# ArduinoSchematic.net
KiCad netlist of a schematic drawn in Altium Designer
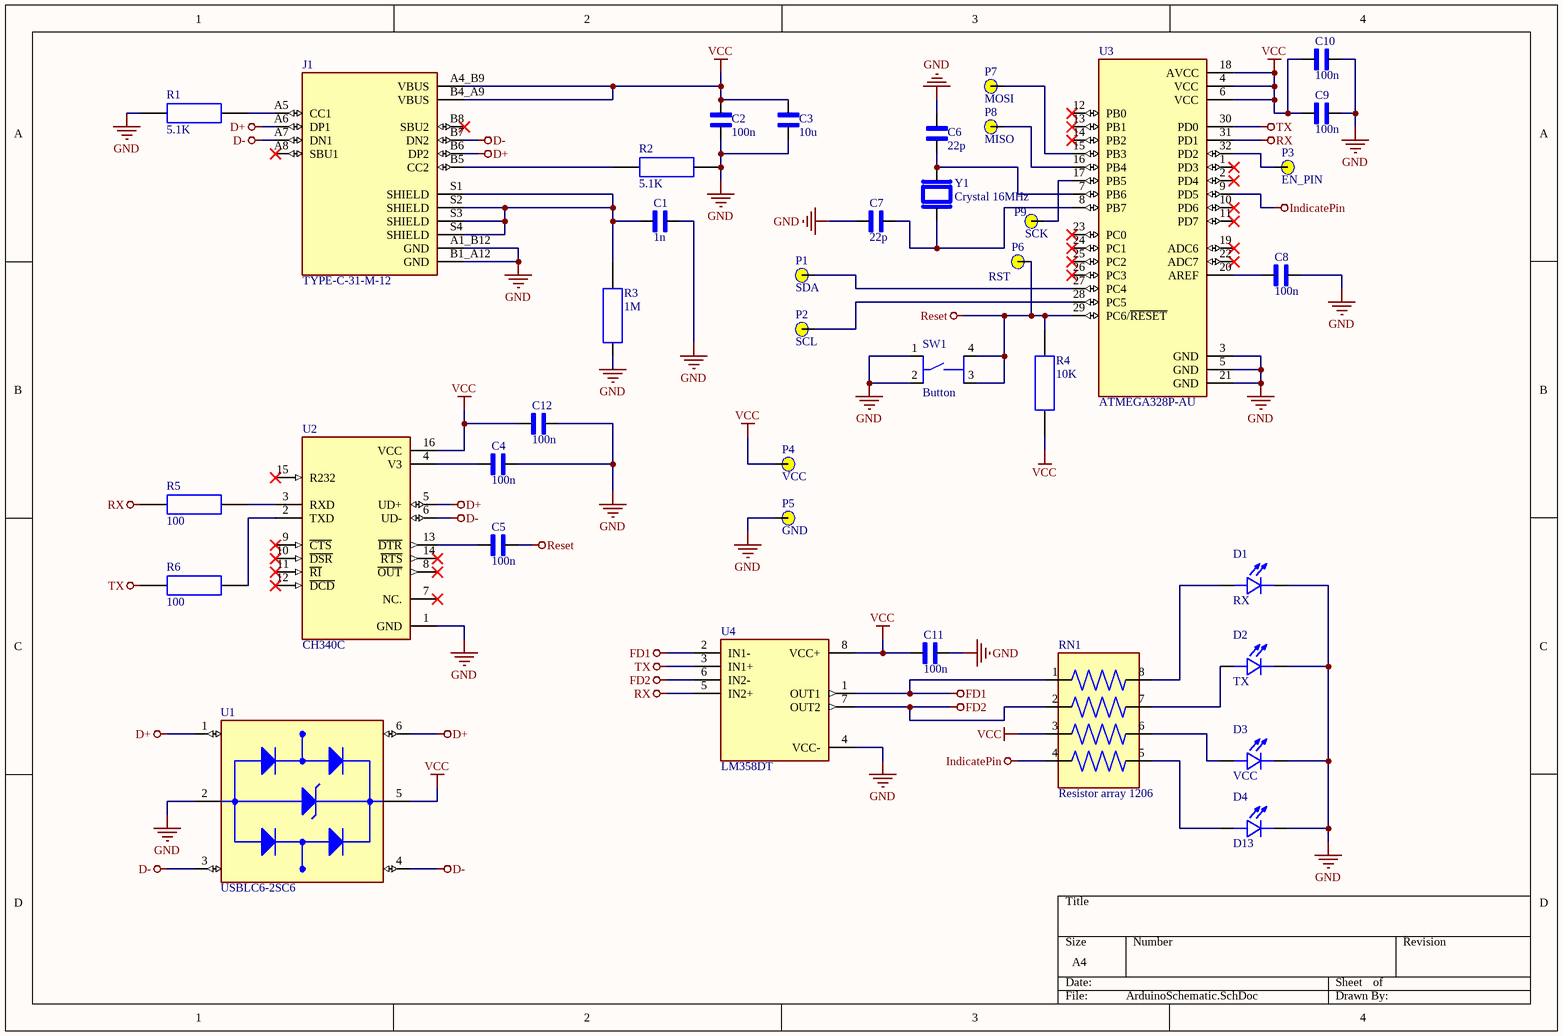
[diagram p0: ArduinoSchematic.SchDoc]

(export (version "E")
  (design (tool "Eeschema 10.0.6"))
  (components
    (comp (ref "C1")
      (value "1n")
      (footprint "Capacitor 1206")
      (fields (field (name "MF") "AVX") (field (name "MP") "12061C225K4T2A"))
      (libsource (lib "") (part "Capacitor 1206_1"))
    )
    (comp (ref "C2")
      (value "100n")
      (footprint "Capacitor 1206")
      (fields (field (name "MF") "AVX") (field (name "MP") "12061C225K4T2A"))
      (libsource (lib "") (part "Capacitor 1206_2"))
    )
    (comp (ref "C3")
      (value "10u")
      (footprint "Capacitor 1206")
      (fields (field (name "MF") "AVX") (field (name "MP") "12061C225K4T2A"))
      (libsource (lib "") (part "Capacitor 1206_2"))
    )
    (comp (ref "C4")
      (value "100n")
      (footprint "Capacitor 1206")
      (fields (field (name "MF") "AVX") (field (name "MP") "12061C225K4T2A"))
      (libsource (lib "") (part "Capacitor 1206_1"))
    )
    (comp (ref "C5")
      (value "100n")
      (footprint "Capacitor 1206")
      (fields (field (name "MF") "AVX") (field (name "MP") "12061C225K4T2A"))
      (libsource (lib "") (part "Capacitor 1206_1"))
    )
    (comp (ref "C6")
      (value "22p")
      (footprint "Capacitor 1206")
      (fields (field (name "MF") "AVX") (field (name "MP") "12061C225K4T2A"))
      (libsource (lib "") (part "Capacitor 1206_2"))
    )
    (comp (ref "C7")
      (value "22p")
      (footprint "Capacitor 1206")
      (fields (field (name "MF") "AVX") (field (name "MP") "12061C225K4T2A"))
      (libsource (lib "Arduinolib") (part "Capacitor 1206"))
    )
    (comp (ref "C8")
      (value "100n")
      (footprint "Capacitor 1206")
      (fields (field (name "MF") "AVX") (field (name "MP") "12061C225K4T2A"))
      (libsource (lib "") (part "Capacitor 1206_1"))
    )
    (comp (ref "C9")
      (value "100n")
      (footprint "Capacitor 1206")
      (fields (field (name "MF") "AVX") (field (name "MP") "12061C225K4T2A"))
      (libsource (lib "") (part "Capacitor 1206_1"))
    )
    (comp (ref "C10")
      (value "100n")
      (footprint "Capacitor 1206")
      (fields (field (name "MF") "AVX") (field (name "MP") "12061C225K4T2A"))
      (libsource (lib "") (part "Capacitor 1206_1"))
    )
    (comp (ref "C11")
      (value "100n")
      (footprint "Capacitor 1206")
      (fields (field (name "MF") "AVX") (field (name "MP") "12061C225K4T2A"))
      (libsource (lib "") (part "Capacitor 1206_1"))
    )
    (comp (ref "C12")
      (value "100n")
      (footprint "Capacitor 1206")
      (fields (field (name "MF") "AVX") (field (name "MP") "12061C225K4T2A"))
      (libsource (lib "") (part "Capacitor 1206_1"))
    )
    (comp (ref "D1")
      (value "RX")
      (footprint "LED 1206")
      (fields (field (name "MF") "Lite-On Inc.") (field (name "MP") "LTST-C230KGKT"))
      (libsource (lib "Arduinolib") (part "LED 1206"))
    )
    (comp (ref "D2")
      (value "TX")
      (footprint "LED 1206")
      (fields (field (name "MF") "Lite-On Inc.") (field (name "MP") "LTST-C230KGKT"))
      (libsource (lib "Arduinolib") (part "LED 1206"))
    )
    (comp (ref "D3")
      (value "VCC")
      (footprint "LED 1206")
      (fields (field (name "MF") "Lite-On Inc.") (field (name "MP") "LTST-C230KGKT"))
      (libsource (lib "Arduinolib") (part "LED 1206"))
    )
    (comp (ref "D4")
      (value "D13")
      (footprint "LED 1206")
      (fields (field (name "MF") "Lite-On Inc.") (field (name "MP") "LTST-C230KGKT"))
      (libsource (lib "Arduinolib") (part "LED 1206"))
    )
    (comp (ref "J1")
      (value "TYPE-C-31-M-12")
      (footprint "HRO_TYPE-C-31-M-12")
      (description "USB Connectors 24 Receptacle 1 8.94*7.3mm RoHS")
      (fields (field (name "MF") "HRO Electronics Co., Ltd."))
      (libsource (lib "Arduinolib") (part "TYPE-C-31-M-12"))
    )
    (comp (ref "P1") (value "SDA") (footprint "PCB_Pin_1") (libsource (lib "Arduinolib") (part "PIN_1")))
    (comp (ref "P2") (value "SCL") (footprint "PCB_Pin_1") (libsource (lib "Arduinolib") (part "PIN_1")))
    (comp (ref "P3") (value "EN_PIN") (footprint "PCB_Pin_1") (libsource (lib "Arduinolib") (part "PIN_1")))
    (comp (ref "P4") (value "VCC") (footprint "PCB_Pin_1") (libsource (lib "Arduinolib") (part "PIN_1")))
    (comp (ref "P5") (value "GND") (footprint "PCB_Pin_1") (libsource (lib "Arduinolib") (part "PIN_1")))
    (comp (ref "P6") (value "RST") (footprint "PCB_Pin_1") (libsource (lib "Arduinolib") (part "PIN_1")))
    (comp (ref "P7") (value "MOSI") (footprint "PCB_Pin_1") (libsource (lib "Arduinolib") (part "PIN_1")))
    (comp (ref "P8") (value "MISO") (footprint "PCB_Pin_1") (libsource (lib "Arduinolib") (part "PIN_1")))
    (comp (ref "P9") (value "SCK") (footprint "PCB_Pin_1") (libsource (lib "Arduinolib") (part "PIN_1")))
    (comp (ref "R1")
      (value "5.1K")
      (footprint "Resistor 1206")
      (fields (field (name "MP") "ERJU08F4703V"))
      (libsource (lib "Arduinolib") (part "Resistor 1206"))
    )
    (comp (ref "R2")
      (value "5.1K")
      (footprint "Resistor 1206")
      (fields (field (name "MP") "ERJU08F4703V"))
      (libsource (lib "Arduinolib") (part "Resistor 1206"))
    )
    (comp (ref "R3")
      (value "1M")
      (footprint "Resistor 1206")
      (fields (field (name "MP") "ERJU08F4703V"))
      (libsource (lib "Arduinolib") (part "Resistor 1206"))
    )
    (comp (ref "R4")
      (value "10K")
      (footprint "Resistor 1206")
      (fields (field (name "MP") "ERJU08F4703V"))
      (libsource (lib "Arduinolib") (part "Resistor 1206"))
    )
    (comp (ref "R5")
      (value "100")
      (footprint "Resistor 1206")
      (fields (field (name "MP") "ERJU08F4703V"))
      (libsource (lib "Arduinolib") (part "Resistor 1206"))
    )
    (comp (ref "R6")
      (value "100")
      (footprint "Resistor 1206")
      (fields (field (name "MP") "ERJU08F4703V"))
      (libsource (lib "Arduinolib") (part "Resistor 1206"))
    )
    (comp (ref "RN1")
      (value "Resistor array 1206")
      (footprint "Resistor array 1206")
      (description "Resistor,Thick Film,Networks & Arrays,330 Ohm,5%,8 Pin ¦ Bourns CAY16-331J4LF")
      (fields (field (name "MF") "Bourns") (field (name "MP") "CAY16-331J4LF"))
      (libsource (lib "Arduinolib") (part "Resistor array 1206"))
    )
    (comp (ref "SW1")
      (value "Button")
      (footprint "Button")
      (description "Tactile Switch SPST-NO Top Actuated Through Hole")
      (fields (field (name "MF") "TE Connectivity ALCOSWITCH Switches") (field (name "MP") "1-1825910-4"))
      (libsource (lib "Arduinolib") (part "Button"))
    )
    (comp (ref "U1")
      (value "USBLC6-2SC6")
      (footprint "USBLC6-2SC6")
      (description "17V Clamp 5A (8/20Âµs) Ipp Tvs Diode Surface Mount SOT-23-6")
      (fields (field (name "MF") "STMicroelectronics"))
      (libsource (lib "Arduinolib") (part "USBLC6-2SC6"))
    )
    (comp (ref "U2")
      (value "CH340C")
      (footprint "CH-340C")
      (description "USB to serial chip CH340")
      (fields (field (name "MF") "WCH"))
      (libsource (lib "Arduinolib") (part "CH340C"))
    )
    (comp (ref "U3")
      (value "ATMEGA328P-AU")
      (footprint "ATMEGA328P-AU")
      (fields (field (name "MF") "Microchip Technology") (field (name "MP") "ATMEGA328PAU"))
      (libsource (lib "Arduinolib") (part "ATMEGA328P-AU"))
    )
    (comp (ref "U4")
      (value "LM358DT")
      (footprint "LM358DT")
      (fields (field (name "MF") "STMicroelectronics"))
      (libsource (lib "Arduinolib") (part "LM358DT"))
    )
    (comp (ref "Y1")
      (value "Crystal 16MHz")
      (footprint "Crystal 16MHz")
      (description "Quartz Crystal, HC-49/U-S Short Package")
      (fields (field (name "MF") "Aker Technology") (field (name "MP") "CA-3.6864-18-3050-X"))
      (libsource (lib "Arduinolib") (part "Crystal 16MHz"))
    )
  )
  (nets
    (net (code "1") (name "D+") (class "Default")
      (node (ref "J1") (pin "A6") (pinfunction "DP1_A6") (pintype "bidirectional"))
      (node (ref "J1") (pin "B6") (pinfunction "DP2_B6") (pintype "bidirectional"))
      (node (ref "U1") (pin "1") (pinfunction "I/O1_IN_1") (pintype "bidirectional"))
      (node (ref "U1") (pin "6") (pinfunction "I/O1_OUT_6") (pintype "bidirectional"))
      (node (ref "U2") (pin "5") (pinfunction "UD+_5") (pintype "bidirectional"))
    )
    (net (code "2") (name "D-") (class "Default")
      (node (ref "J1") (pin "A7") (pinfunction "DN1_A7") (pintype "bidirectional"))
      (node (ref "J1") (pin "B7") (pinfunction "DN2_B7") (pintype "bidirectional"))
      (node (ref "U1") (pin "3") (pinfunction "I/O2_IN_3") (pintype "bidirectional"))
      (node (ref "U1") (pin "4") (pinfunction "I/O2_OUT_4") (pintype "bidirectional"))
      (node (ref "U2") (pin "6") (pinfunction "UD-_6") (pintype "bidirectional"))
    )
    (net (code "3") (name "FD1") (class "Default")
      (node (ref "RN1") (pin "1") (pinfunction "1_1") (pintype "passive"))
      (node (ref "U4") (pin "1") (pinfunction "OUT1_1") (pintype "output"))
      (node (ref "U4") (pin "2") (pinfunction "IN1-_2") (pintype "passive"))
    )
    (net (code "4") (name "FD2") (class "Default")
      (node (ref "RN1") (pin "2") (pinfunction "2_2") (pintype "passive"))
      (node (ref "U4") (pin "6") (pinfunction "IN2-_6") (pintype "passive"))
      (node (ref "U4") (pin "7") (pinfunction "OUT2_7") (pintype "output"))
    )
    (net (code "5") (name "GND") (class "Default")
      (node (ref "C1") (pin "2") (pinfunction "2_2") (pintype "passive"))
      (node (ref "C10") (pin "2") (pinfunction "2_2") (pintype "passive"))
      (node (ref "C11") (pin "2") (pinfunction "2_2") (pintype "passive"))
      (node (ref "C12") (pin "2") (pinfunction "2_2") (pintype "passive"))
      (node (ref "C2") (pin "1") (pinfunction "1_1") (pintype "passive"))
      (node (ref "C3") (pin "1") (pinfunction "1_1") (pintype "passive"))
      (node (ref "C4") (pin "2") (pinfunction "2_2") (pintype "passive"))
      (node (ref "C6") (pin "2") (pinfunction "2_2") (pintype "passive"))
      (node (ref "C7") (pin "2") (pinfunction "2_2") (pintype "passive"))
      (node (ref "C8") (pin "2") (pinfunction "2_2") (pintype "passive"))
      (node (ref "C9") (pin "2") (pinfunction "2_2") (pintype "passive"))
      (node (ref "D1") (pin "C") (pinfunction "C_C") (pintype "passive"))
      (node (ref "D2") (pin "C") (pinfunction "C_C") (pintype "passive"))
      (node (ref "D3") (pin "C") (pinfunction "C_C") (pintype "passive"))
      (node (ref "D4") (pin "C") (pinfunction "C_C") (pintype "passive"))
      (node (ref "J1") (pin "A1_B12") (pinfunction "GND_A1_B12") (pintype "power_in"))
      (node (ref "J1") (pin "B1_A12") (pinfunction "GND_B1_A12") (pintype "power_in"))
      (node (ref "P5") (pin "0") (pinfunction "Pin_0") (pintype "passive"))
      (node (ref "R1") (pin "1") (pinfunction "1_1") (pintype "passive"))
      (node (ref "R2") (pin "2") (pinfunction "2_2") (pintype "passive"))
      (node (ref "R3") (pin "1") (pinfunction "1_1") (pintype "passive"))
      (node (ref "SW1") (pin "1") (pinfunction "1_1") (pintype "passive"))
      (node (ref "SW1") (pin "2") (pinfunction "2_2") (pintype "passive"))
      (node (ref "U1") (pin "2") (pinfunction "GND_2") (pintype "power_in"))
      (node (ref "U2") (pin "1") (pinfunction "GND_1") (pintype "power_in"))
      (node (ref "U3") (pin "21") (pinfunction "GND_21") (pintype "power_in"))
      (node (ref "U3") (pin "3") (pinfunction "GND_3") (pintype "power_in"))
      (node (ref "U3") (pin "5") (pinfunction "GND_5") (pintype "power_in"))
      (node (ref "U4") (pin "4") (pinfunction "VCC-_4") (pintype "power_in"))
    )
    (net (code "6") (name "IndicatePin") (class "Default")
      (node (ref "RN1") (pin "4") (pinfunction "4_4") (pintype "passive"))
      (node (ref "U3") (pin "9") (pinfunction "PD5_9") (pintype "bidirectional"))
    )
    (net (code "7") (name "Net-(C1-Pad1)") (class "Default")
      (node (ref "C1") (pin "1") (pinfunction "1_1") (pintype "passive"))
      (node (ref "J1") (pin "S1") (pinfunction "SHIELD_S1") (pintype "passive"))
      (node (ref "J1") (pin "S2") (pinfunction "SHIELD_S2") (pintype "passive"))
      (node (ref "J1") (pin "S3") (pinfunction "SHIELD_S3") (pintype "passive"))
      (node (ref "J1") (pin "S4") (pinfunction "SHIELD_S4") (pintype "passive"))
      (node (ref "R3") (pin "2") (pinfunction "2_2") (pintype "passive"))
    )
    (net (code "8") (name "Net-(D1-PadA)") (class "Default")
      (node (ref "D1") (pin "A") (pinfunction "A_A") (pintype "passive"))
      (node (ref "RN1") (pin "8") (pinfunction "8_8") (pintype "passive"))
    )
    (net (code "9") (name "Net-(D2-PadA)") (class "Default")
      (node (ref "D2") (pin "A") (pinfunction "A_A") (pintype "passive"))
      (node (ref "RN1") (pin "7") (pinfunction "7_7") (pintype "passive"))
    )
    (net (code "10") (name "Net-(D3-PadA)") (class "Default")
      (node (ref "D3") (pin "A") (pinfunction "A_A") (pintype "passive"))
      (node (ref "RN1") (pin "6") (pinfunction "6_6") (pintype "passive"))
    )
    (net (code "11") (name "Net-(D4-PadA)") (class "Default")
      (node (ref "D4") (pin "A") (pinfunction "A_A") (pintype "passive"))
      (node (ref "RN1") (pin "5") (pinfunction "5_5") (pintype "passive"))
    )
    (net (code "12") (name "Net-(J1-CC1)") (class "Default")
      (node (ref "J1") (pin "A5") (pinfunction "CC1_A5") (pintype "bidirectional"))
      (node (ref "R1") (pin "2") (pinfunction "2_2") (pintype "passive"))
    )
    (net (code "13") (name "Net-(J1-CC2)") (class "Default")
      (node (ref "J1") (pin "B5") (pinfunction "CC2_B5") (pintype "bidirectional"))
      (node (ref "R2") (pin "1") (pinfunction "1_1") (pintype "passive"))
    )
    (net (code "14") (name "Net-(P1-Pin)") (class "Default")
      (node (ref "P1") (pin "0") (pinfunction "Pin_0") (pintype "passive"))
      (node (ref "U3") (pin "27") (pinfunction "PC4_27") (pintype "bidirectional"))
    )
    (net (code "15") (name "Net-(P2-Pin)") (class "Default")
      (node (ref "P2") (pin "0") (pinfunction "Pin_0") (pintype "passive"))
      (node (ref "U3") (pin "28") (pinfunction "PC5_28") (pintype "bidirectional"))
    )
    (net (code "16") (name "Net-(P3-Pin)") (class "Default")
      (node (ref "P3") (pin "0") (pinfunction "Pin_0") (pintype "passive"))
      (node (ref "U3") (pin "32") (pinfunction "PD2_32") (pintype "bidirectional"))
    )
    (net (code "17") (name "Net-(P7-Pin)") (class "Default")
      (node (ref "P7") (pin "0") (pinfunction "Pin_0") (pintype "passive"))
      (node (ref "U3") (pin "15") (pinfunction "PB3_15") (pintype "bidirectional"))
    )
    (net (code "18") (name "Net-(P8-Pin)") (class "Default")
      (node (ref "P8") (pin "0") (pinfunction "Pin_0") (pintype "passive"))
      (node (ref "U3") (pin "16") (pinfunction "PB4_16") (pintype "bidirectional"))
    )
    (net (code "19") (name "Net-(P9-Pin)") (class "Default")
      (node (ref "P9") (pin "0") (pinfunction "Pin_0") (pintype "passive"))
      (node (ref "U3") (pin "17") (pinfunction "PB5_17") (pintype "bidirectional"))
    )
    (net (code "20") (name "Net-(U2-RXD)") (class "Default")
      (node (ref "R5") (pin "2") (pinfunction "2_2") (pintype "passive"))
      (node (ref "U2") (pin "3") (pinfunction "RXD_3") (pintype "passive"))
    )
    (net (code "21") (name "Net-(U2-TXD)") (class "Default")
      (node (ref "R6") (pin "2") (pinfunction "2_2") (pintype "passive"))
      (node (ref "U2") (pin "2") (pinfunction "TXD_2") (pintype "passive"))
    )
    (net (code "22") (name "Net-(U2-V3)") (class "Default")
      (node (ref "C4") (pin "1") (pinfunction "1_1") (pintype "passive"))
      (node (ref "U2") (pin "4") (pinfunction "V3_4") (pintype "power_in"))
    )
    (net (code "23") (name "Net-(U2-~{DTR})") (class "Default")
      (node (ref "C5") (pin "1") (pinfunction "1_1") (pintype "passive"))
      (node (ref "U2") (pin "13") (pinfunction "~{DTR}_13") (pintype "output"))
    )
    (net (code "24") (name "Net-(U3-AREF)") (class "Default")
      (node (ref "C8") (pin "1") (pinfunction "1_1") (pintype "passive"))
      (node (ref "U3") (pin "20") (pinfunction "AREF_20") (pintype "passive"))
    )
    (net (code "25") (name "Net-(U3-PB6)") (class "Default")
      (node (ref "C6") (pin "1") (pinfunction "1_1") (pintype "passive"))
      (node (ref "U3") (pin "7") (pinfunction "PB6_7") (pintype "bidirectional"))
      (node (ref "Y1") (pin "2") (pinfunction "2_2") (pintype "passive"))
    )
    (net (code "26") (name "Net-(U3-PB7)") (class "Default")
      (node (ref "C7") (pin "1") (pinfunction "1_1") (pintype "passive"))
      (node (ref "U3") (pin "8") (pinfunction "PB7_8") (pintype "bidirectional"))
      (node (ref "Y1") (pin "1") (pinfunction "1_1") (pintype "passive"))
    )
    (net (code "27") (name "RX") (class "Default")
      (node (ref "R5") (pin "1") (pinfunction "1_1") (pintype "passive"))
      (node (ref "U3") (pin "31") (pinfunction "PD1_31") (pintype "passive"))
      (node (ref "U4") (pin "5") (pinfunction "IN2+_5") (pintype "passive"))
    )
    (net (code "28") (name "Reset") (class "Default")
      (node (ref "C5") (pin "2") (pinfunction "2_2") (pintype "passive"))
      (node (ref "P6") (pin "0") (pinfunction "Pin_0") (pintype "passive"))
      (node (ref "R4") (pin "2") (pinfunction "2_2") (pintype "passive"))
      (node (ref "SW1") (pin "3") (pinfunction "3_3") (pintype "passive"))
      (node (ref "SW1") (pin "4") (pinfunction "4_4") (pintype "passive"))
      (node (ref "U3") (pin "29") (pinfunction "PC6/~{RESET}_29") (pintype "bidirectional"))
    )
    (net (code "29") (name "TX") (class "Default")
      (node (ref "R6") (pin "1") (pinfunction "1_1") (pintype "passive"))
      (node (ref "U3") (pin "30") (pinfunction "PD0_30") (pintype "passive"))
      (node (ref "U4") (pin "3") (pinfunction "IN1+_3") (pintype "passive"))
    )
    (net (code "30") (name "VCC") (class "Default")
      (node (ref "C10") (pin "1") (pinfunction "1_1") (pintype "passive"))
      (node (ref "C11") (pin "1") (pinfunction "1_1") (pintype "passive"))
      (node (ref "C12") (pin "1") (pinfunction "1_1") (pintype "passive"))
      (node (ref "C2") (pin "2") (pinfunction "2_2") (pintype "passive"))
      (node (ref "C3") (pin "2") (pinfunction "2_2") (pintype "passive"))
      (node (ref "C9") (pin "1") (pinfunction "1_1") (pintype "passive"))
      (node (ref "J1") (pin "A4_B9") (pinfunction "VBUS_A4_B9") (pintype "power_in"))
      (node (ref "J1") (pin "B4_A9") (pinfunction "VBUS_B4_A9") (pintype "power_in"))
      (node (ref "P4") (pin "0") (pinfunction "Pin_0") (pintype "passive"))
      (node (ref "R4") (pin "1") (pinfunction "1_1") (pintype "passive"))
      (node (ref "RN1") (pin "3") (pinfunction "3_3") (pintype "passive"))
      (node (ref "U1") (pin "5") (pinfunction "VBUS_5") (pintype "power_in"))
      (node (ref "U2") (pin "16") (pinfunction "VCC_16") (pintype "power_in"))
      (node (ref "U3") (pin "18") (pinfunction "AVCC_18") (pintype "power_in"))
      (node (ref "U3") (pin "4") (pinfunction "VCC_4") (pintype "power_in"))
      (node (ref "U3") (pin "6") (pinfunction "VCC_6") (pintype "power_in"))
      (node (ref "U4") (pin "8") (pinfunction "VCC+_8") (pintype "power_in"))
    )
    (net (code "31") (name "unconnected-(J1-SBU1-PadA8)") (class "Default")
      (node (ref "J1") (pin "A8") (pinfunction "SBU1_A8") (pintype "bidirectional+no_connect"))
    )
    (net (code "32") (name "unconnected-(J1-SBU2-PadB8)") (class "Default")
      (node (ref "J1") (pin "B8") (pinfunction "SBU2_B8") (pintype "bidirectional+no_connect"))
    )
    (net (code "33") (name "unconnected-(U2-NC.-Pad7)") (class "Default")
      (node (ref "U2") (pin "7") (pinfunction "NC._7") (pintype "passive+no_connect"))
    )
    (net (code "34") (name "unconnected-(U2-R232-Pad15)") (class "Default")
      (node (ref "U2") (pin "15") (pinfunction "R232_15") (pintype "input+no_connect"))
    )
    (net (code "35") (name "unconnected-(U2-~{CTS}-Pad9)") (class "Default")
      (node (ref "U2") (pin "9") (pinfunction "~{CTS}_9") (pintype "input+no_connect"))
    )
    (net (code "36") (name "unconnected-(U2-~{DCD}-Pad12)") (class "Default")
      (node (ref "U2") (pin "12") (pinfunction "~{DCD}_12") (pintype "input+no_connect"))
    )
    (net (code "37") (name "unconnected-(U2-~{DSR}-Pad10)") (class "Default")
      (node (ref "U2") (pin "10") (pinfunction "~{DSR}_10") (pintype "input+no_connect"))
    )
    (net (code "38") (name "unconnected-(U2-~{OUT}-Pad8)") (class "Default")
      (node (ref "U2") (pin "8") (pinfunction "~{OUT}_8") (pintype "output+no_connect"))
    )
    (net (code "39") (name "unconnected-(U2-~{RI}-Pad11)") (class "Default")
      (node (ref "U2") (pin "11") (pinfunction "~{RI}_11") (pintype "input+no_connect"))
    )
    (net (code "40") (name "unconnected-(U2-~{RTS}-Pad14)") (class "Default")
      (node (ref "U2") (pin "14") (pinfunction "~{RTS}_14") (pintype "output+no_connect"))
    )
    (net (code "41") (name "unconnected-(U3-ADC6-Pad19)") (class "Default")
      (node (ref "U3") (pin "19") (pinfunction "ADC6_19") (pintype "bidirectional+no_connect"))
    )
    (net (code "42") (name "unconnected-(U3-ADC7-Pad22)") (class "Default")
      (node (ref "U3") (pin "22") (pinfunction "ADC7_22") (pintype "bidirectional+no_connect"))
    )
    (net (code "43") (name "unconnected-(U3-PB0-Pad12)") (class "Default")
      (node (ref "U3") (pin "12") (pinfunction "PB0_12") (pintype "bidirectional+no_connect"))
    )
    (net (code "44") (name "unconnected-(U3-PB1-Pad13)") (class "Default")
      (node (ref "U3") (pin "13") (pinfunction "PB1_13") (pintype "bidirectional+no_connect"))
    )
    (net (code "45") (name "unconnected-(U3-PB2-Pad14)") (class "Default")
      (node (ref "U3") (pin "14") (pinfunction "PB2_14") (pintype "bidirectional+no_connect"))
    )
    (net (code "46") (name "unconnected-(U3-PC0-Pad23)") (class "Default")
      (node (ref "U3") (pin "23") (pinfunction "PC0_23") (pintype "bidirectional+no_connect"))
    )
    (net (code "47") (name "unconnected-(U3-PC1-Pad24)") (class "Default")
      (node (ref "U3") (pin "24") (pinfunction "PC1_24") (pintype "bidirectional+no_connect"))
    )
    (net (code "48") (name "unconnected-(U3-PC2-Pad25)") (class "Default")
      (node (ref "U3") (pin "25") (pinfunction "PC2_25") (pintype "bidirectional+no_connect"))
    )
    (net (code "49") (name "unconnected-(U3-PC3-Pad26)") (class "Default")
      (node (ref "U3") (pin "26") (pinfunction "PC3_26") (pintype "bidirectional+no_connect"))
    )
    (net (code "50") (name "unconnected-(U3-PD3-Pad1)") (class "Default")
      (node (ref "U3") (pin "1") (pinfunction "PD3_1") (pintype "bidirectional+no_connect"))
    )
    (net (code "51") (name "unconnected-(U3-PD4-Pad2)") (class "Default")
      (node (ref "U3") (pin "2") (pinfunction "PD4_2") (pintype "bidirectional+no_connect"))
    )
    (net (code "52") (name "unconnected-(U3-PD6-Pad10)") (class "Default")
      (node (ref "U3") (pin "10") (pinfunction "PD6_10") (pintype "bidirectional+no_connect"))
    )
    (net (code "53") (name "unconnected-(U3-PD7-Pad11)") (class "Default")
      (node (ref "U3") (pin "11") (pinfunction "PD7_11") (pintype "bidirectional+no_connect"))
    )
  )
)
